# CSM_Esquematico.net
KiCad netlist of a schematic drawn in Altium Designer
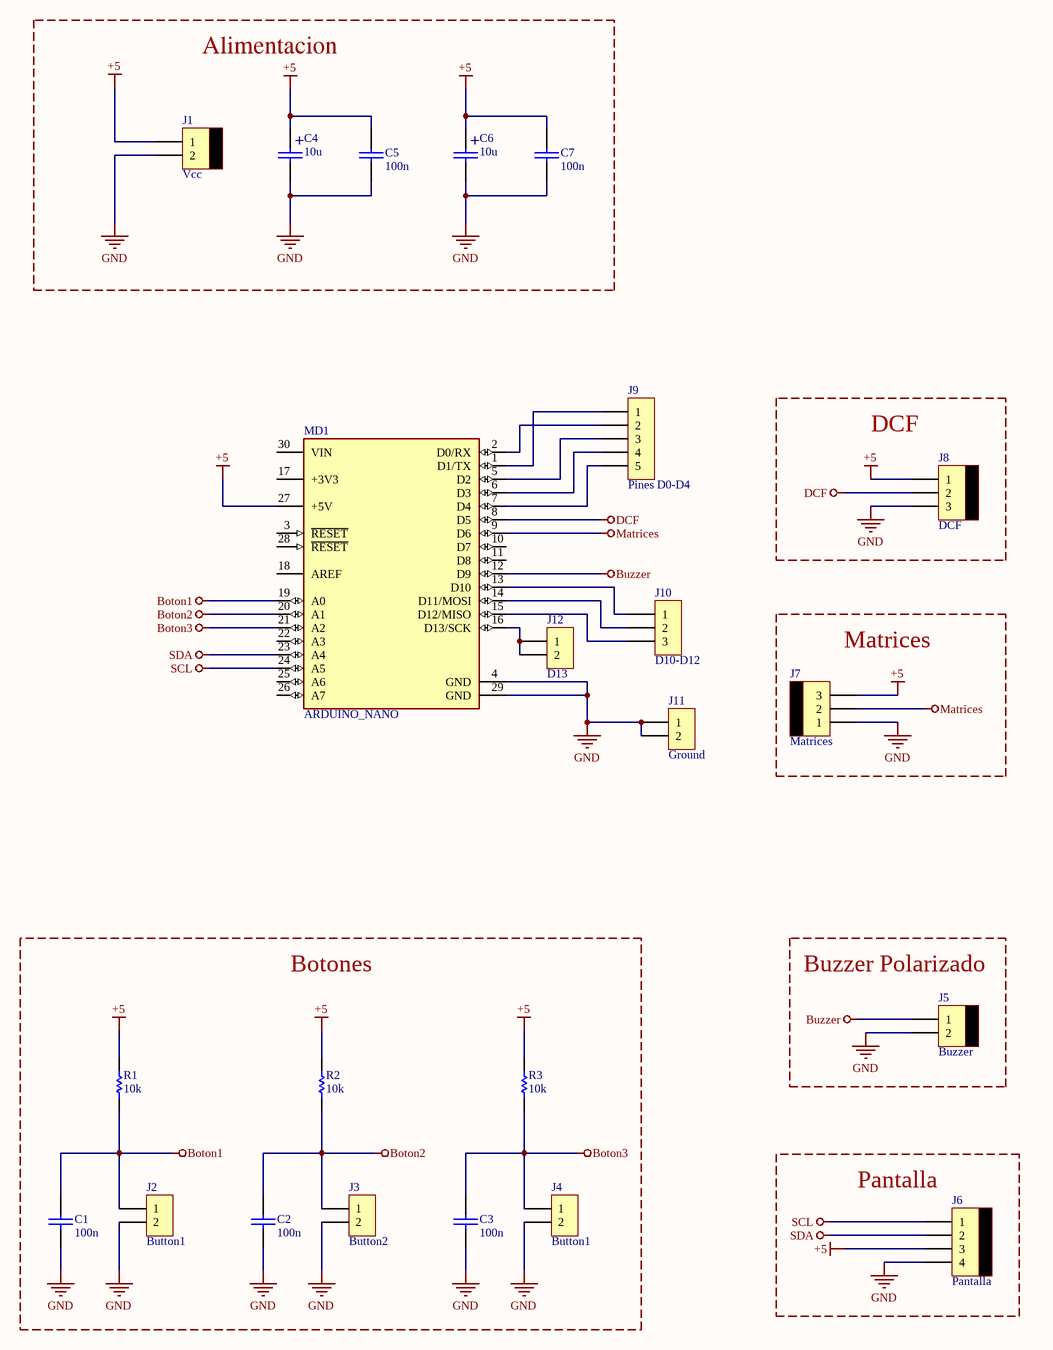
[diagram p0: CSM_Esquematico.SchDoc]

(export (version "E")
  (design (tool "Eeschema 10.0.6"))
  (components
    (comp (ref "C1") (value "100n") (footprint "0805") (libsource (lib "LIBEBAL") (part "CAP")))
    (comp (ref "C2") (value "100n") (footprint "0805") (libsource (lib "LIBEBAL") (part "CAP")))
    (comp (ref "C3") (value "100n") (footprint "0805") (libsource (lib "LIBEBAL") (part "CAP")))
    (comp (ref "C4") (value "10u") (footprint "CAP100RP") (libsource (lib "LIBEBAL") (part "CAPPOL")))
    (comp (ref "C5") (value "100n") (footprint "CAP200") (libsource (lib "LIBEBAL") (part "CAP")))
    (comp (ref "C6") (value "10u") (footprint "CAP100RP") (libsource (lib "LIBEBAL") (part "CAPPOL")))
    (comp (ref "C7") (value "100n") (footprint "CAP200") (libsource (lib "LIBEBAL") (part "CAP")))
    (comp (ref "J1")
      (value "Vcc")
      (footprint "MOLEX2")
      (description "Tensión de alimentación")
      (libsource (lib "LIBEBAL") (part "MOLEX2"))
    )
    (comp (ref "J2") (value "Button1") (footprint "SIP2") (libsource (lib "LIBEBAL") (part "CON2")))
    (comp (ref "J3") (value "Button2") (footprint "SIP2") (libsource (lib "LIBEBAL") (part "CON2")))
    (comp (ref "J4") (value "Button1") (footprint "SIP2") (libsource (lib "LIBEBAL") (part "CON2")))
    (comp (ref "J5") (value "Buzzer") (footprint "MOLEX2") (libsource (lib "LIBEBAL") (part "MOLEX2")))
    (comp (ref "J6") (value "Pantalla") (footprint "MOLEX4") (libsource (lib "LIBEBAL") (part "MOLEX4")))
    (comp (ref "J7") (value "Matrices") (footprint "MOLEX3") (libsource (lib "LIBEBAL") (part "MOLEX3")))
    (comp (ref "J8") (value "DCF") (footprint "MOLEX3") (libsource (lib "") (part "MOLEX3_1")))
    (comp (ref "J9") (value "Pines D0-D4") (footprint "SIP5") (libsource (lib "LIBEBAL") (part "CON5")))
    (comp (ref "J10") (value "D10-D12") (footprint "SIP3") (libsource (lib "LIBEBAL") (part "CON3")))
    (comp (ref "J11") (value "Ground") (footprint "SIP2") (libsource (lib "LIBEBAL") (part "CON2")))
    (comp (ref "J12") (value "D13") (footprint "SIP2") (libsource (lib "LIBEBAL") (part "CON2")))
    (comp (ref "MD1")
      (value "ARDUINO_NANO")
      (footprint "FP-A000005-MFG")
      (description "ARDUINO NANO ATMEGA328 EVAL BRD")
      (libsource (lib "Altium Content Vault") (part "d190c066e99afd1c6882cf92e11b2cc"))
    )
    (comp (ref "R1") (value "10k") (footprint "0805") (libsource (lib "LIBEBAL") (part "RES")))
    (comp (ref "R2") (value "10k") (footprint "0805") (libsource (lib "LIBEBAL") (part "RES")))
    (comp (ref "R3") (value "10k") (footprint "0805") (libsource (lib "LIBEBAL") (part "RES")))
  )
  (nets
    (net (code "1") (name "+5") (class "Default")
      (node (ref "C4") (pin "1") (pinfunction "1_1") (pintype "passive"))
      (node (ref "C5") (pin "1") (pinfunction "1_1") (pintype "passive"))
      (node (ref "C6") (pin "1") (pinfunction "1_1") (pintype "passive"))
      (node (ref "C7") (pin "1") (pinfunction "1_1") (pintype "passive"))
      (node (ref "J1") (pin "1") (pinfunction "1_1") (pintype "passive"))
      (node (ref "J6") (pin "3") (pinfunction "3_3") (pintype "passive"))
      (node (ref "J7") (pin "3") (pinfunction "3_3") (pintype "passive"))
      (node (ref "J8") (pin "1") (pinfunction "1_1") (pintype "passive"))
      (node (ref "MD1") (pin "27") (pinfunction "+5V_27") (pintype "power_in"))
      (node (ref "R1") (pin "1") (pinfunction "1_1") (pintype "passive"))
      (node (ref "R2") (pin "1") (pinfunction "1_1") (pintype "passive"))
      (node (ref "R3") (pin "1") (pinfunction "1_1") (pintype "passive"))
    )
    (net (code "2") (name "Boton1") (class "Default")
      (node (ref "C1") (pin "1") (pinfunction "1_1") (pintype "passive"))
      (node (ref "J2") (pin "1") (pinfunction "1_1") (pintype "passive"))
      (node (ref "MD1") (pin "19") (pinfunction "A0_19") (pintype "bidirectional"))
      (node (ref "R1") (pin "2") (pinfunction "2_2") (pintype "passive"))
    )
    (net (code "3") (name "Boton2") (class "Default")
      (node (ref "C2") (pin "1") (pinfunction "1_1") (pintype "passive"))
      (node (ref "J3") (pin "1") (pinfunction "1_1") (pintype "passive"))
      (node (ref "MD1") (pin "20") (pinfunction "A1_20") (pintype "bidirectional"))
      (node (ref "R2") (pin "2") (pinfunction "2_2") (pintype "passive"))
    )
    (net (code "4") (name "Boton3") (class "Default")
      (node (ref "C3") (pin "1") (pinfunction "1_1") (pintype "passive"))
      (node (ref "J4") (pin "1") (pinfunction "1_1") (pintype "passive"))
      (node (ref "MD1") (pin "21") (pinfunction "A2_21") (pintype "bidirectional"))
      (node (ref "R3") (pin "2") (pinfunction "2_2") (pintype "passive"))
    )
    (net (code "5") (name "Buzzer") (class "Default")
      (node (ref "J5") (pin "1") (pinfunction "1_1") (pintype "passive"))
      (node (ref "MD1") (pin "12") (pinfunction "D9_12") (pintype "bidirectional"))
    )
    (net (code "6") (name "DCF") (class "Default")
      (node (ref "J8") (pin "2") (pinfunction "2_2") (pintype "passive"))
      (node (ref "MD1") (pin "8") (pinfunction "D5_8") (pintype "bidirectional"))
    )
    (net (code "7") (name "GND") (class "Default")
      (node (ref "C1") (pin "2") (pinfunction "2_2") (pintype "passive"))
      (node (ref "C2") (pin "2") (pinfunction "2_2") (pintype "passive"))
      (node (ref "C3") (pin "2") (pinfunction "2_2") (pintype "passive"))
      (node (ref "C4") (pin "2") (pinfunction "2_2") (pintype "passive"))
      (node (ref "C5") (pin "2") (pinfunction "2_2") (pintype "passive"))
      (node (ref "C6") (pin "2") (pinfunction "2_2") (pintype "passive"))
      (node (ref "C7") (pin "2") (pinfunction "2_2") (pintype "passive"))
      (node (ref "J1") (pin "2") (pinfunction "2_2") (pintype "passive"))
      (node (ref "J11") (pin "1") (pinfunction "1_1") (pintype "passive"))
      (node (ref "J11") (pin "2") (pinfunction "2_2") (pintype "passive"))
      (node (ref "J2") (pin "2") (pinfunction "2_2") (pintype "passive"))
      (node (ref "J3") (pin "2") (pinfunction "2_2") (pintype "passive"))
      (node (ref "J4") (pin "2") (pinfunction "2_2") (pintype "passive"))
      (node (ref "J5") (pin "2") (pinfunction "2_2") (pintype "passive"))
      (node (ref "J6") (pin "4") (pinfunction "4_4") (pintype "passive"))
      (node (ref "J7") (pin "1") (pinfunction "1_1") (pintype "passive"))
      (node (ref "J8") (pin "3") (pinfunction "3_3") (pintype "passive"))
      (node (ref "MD1") (pin "29") (pinfunction "GND_29") (pintype "power_in"))
      (node (ref "MD1") (pin "4") (pinfunction "GND_4") (pintype "power_in"))
    )
    (net (code "8") (name "Matrices") (class "Default")
      (node (ref "J7") (pin "2") (pinfunction "2_2") (pintype "passive"))
      (node (ref "MD1") (pin "9") (pinfunction "D6_9") (pintype "bidirectional"))
    )
    (net (code "9") (name "Net-(MD1-D0{slash}RX)") (class "Default")
      (node (ref "J9") (pin "2") (pinfunction "2_2") (pintype "passive"))
      (node (ref "MD1") (pin "2") (pinfunction "D0/RX_2") (pintype "bidirectional"))
    )
    (net (code "10") (name "Net-(MD1-D1{slash}TX)") (class "Default")
      (node (ref "J9") (pin "1") (pinfunction "1_1") (pintype "passive"))
      (node (ref "MD1") (pin "1") (pinfunction "D1/TX_1") (pintype "bidirectional"))
    )
    (net (code "11") (name "Net-(MD1-D2)") (class "Default")
      (node (ref "J9") (pin "3") (pinfunction "3_3") (pintype "passive"))
      (node (ref "MD1") (pin "5") (pinfunction "D2_5") (pintype "bidirectional"))
    )
    (net (code "12") (name "Net-(MD1-D3)") (class "Default")
      (node (ref "J9") (pin "4") (pinfunction "4_4") (pintype "passive"))
      (node (ref "MD1") (pin "6") (pinfunction "D3_6") (pintype "bidirectional"))
    )
    (net (code "13") (name "Net-(MD1-D4)") (class "Default")
      (node (ref "J9") (pin "5") (pinfunction "5_5") (pintype "passive"))
      (node (ref "MD1") (pin "7") (pinfunction "D4_7") (pintype "bidirectional"))
    )
    (net (code "14") (name "Net-(MD1-D10)") (class "Default")
      (node (ref "J10") (pin "1") (pinfunction "1_1") (pintype "passive"))
      (node (ref "MD1") (pin "13") (pinfunction "D10_13") (pintype "bidirectional"))
    )
    (net (code "15") (name "Net-(MD1-D11{slash}MOSI)") (class "Default")
      (node (ref "J10") (pin "2") (pinfunction "2_2") (pintype "passive"))
      (node (ref "MD1") (pin "14") (pinfunction "D11/MOSI_14") (pintype "bidirectional"))
    )
    (net (code "16") (name "Net-(MD1-D12{slash}MISO)") (class "Default")
      (node (ref "J10") (pin "3") (pinfunction "3_3") (pintype "passive"))
      (node (ref "MD1") (pin "15") (pinfunction "D12/MISO_15") (pintype "bidirectional"))
    )
    (net (code "17") (name "Net-(MD1-D13{slash}SCK)") (class "Default")
      (node (ref "J12") (pin "1") (pinfunction "1_1") (pintype "passive"))
      (node (ref "J12") (pin "2") (pinfunction "2_2") (pintype "passive"))
      (node (ref "MD1") (pin "16") (pinfunction "D13/SCK_16") (pintype "bidirectional"))
    )
    (net (code "18") (name "SCL") (class "Default")
      (node (ref "J6") (pin "1") (pinfunction "1_1") (pintype "passive"))
      (node (ref "MD1") (pin "24") (pinfunction "A5_24") (pintype "bidirectional"))
    )
    (net (code "19") (name "SDA") (class "Default")
      (node (ref "J6") (pin "2") (pinfunction "2_2") (pintype "passive"))
      (node (ref "MD1") (pin "23") (pinfunction "A4_23") (pintype "bidirectional"))
    )
    (net (code "20") (name "unconnected-(MD1-+3V3-Pad17)") (class "Default")
      (node (ref "MD1") (pin "17") (pinfunction "+3V3_17") (pintype "power_in"))
    )
    (net (code "21") (name "unconnected-(MD1-A3-Pad22)") (class "Default")
      (node (ref "MD1") (pin "22") (pinfunction "A3_22") (pintype "bidirectional"))
    )
    (net (code "22") (name "unconnected-(MD1-A6-Pad25)") (class "Default")
      (node (ref "MD1") (pin "25") (pinfunction "A6_25") (pintype "bidirectional"))
    )
    (net (code "23") (name "unconnected-(MD1-A7-Pad26)") (class "Default")
      (node (ref "MD1") (pin "26") (pinfunction "A7_26") (pintype "bidirectional"))
    )
    (net (code "24") (name "unconnected-(MD1-AREF-Pad18)") (class "Default")
      (node (ref "MD1") (pin "18") (pinfunction "AREF_18") (pintype "passive"))
    )
    (net (code "25") (name "unconnected-(MD1-D7-Pad10)") (class "Default")
      (node (ref "MD1") (pin "10") (pinfunction "D7_10") (pintype "bidirectional"))
    )
    (net (code "26") (name "unconnected-(MD1-D8-Pad11)") (class "Default")
      (node (ref "MD1") (pin "11") (pinfunction "D8_11") (pintype "bidirectional"))
    )
    (net (code "27") (name "unconnected-(MD1-VIN-Pad30)") (class "Default")
      (node (ref "MD1") (pin "30") (pinfunction "VIN_30") (pintype "power_in"))
    )
    (net (code "28") (name "unconnected-(MD1-~{RESET}-Pad3)") (class "Default")
      (node (ref "MD1") (pin "3") (pinfunction "~{RESET}_3") (pintype "input"))
    )
    (net (code "29") (name "unconnected-(MD1-~{RESET}-Pad28)") (class "Default")
      (node (ref "MD1") (pin "28") (pinfunction "~{RESET}_28") (pintype "input"))
    )
  )
)
